# Zusatzplatine.net
KiCad netlist of a schematic drawn in EAGLE
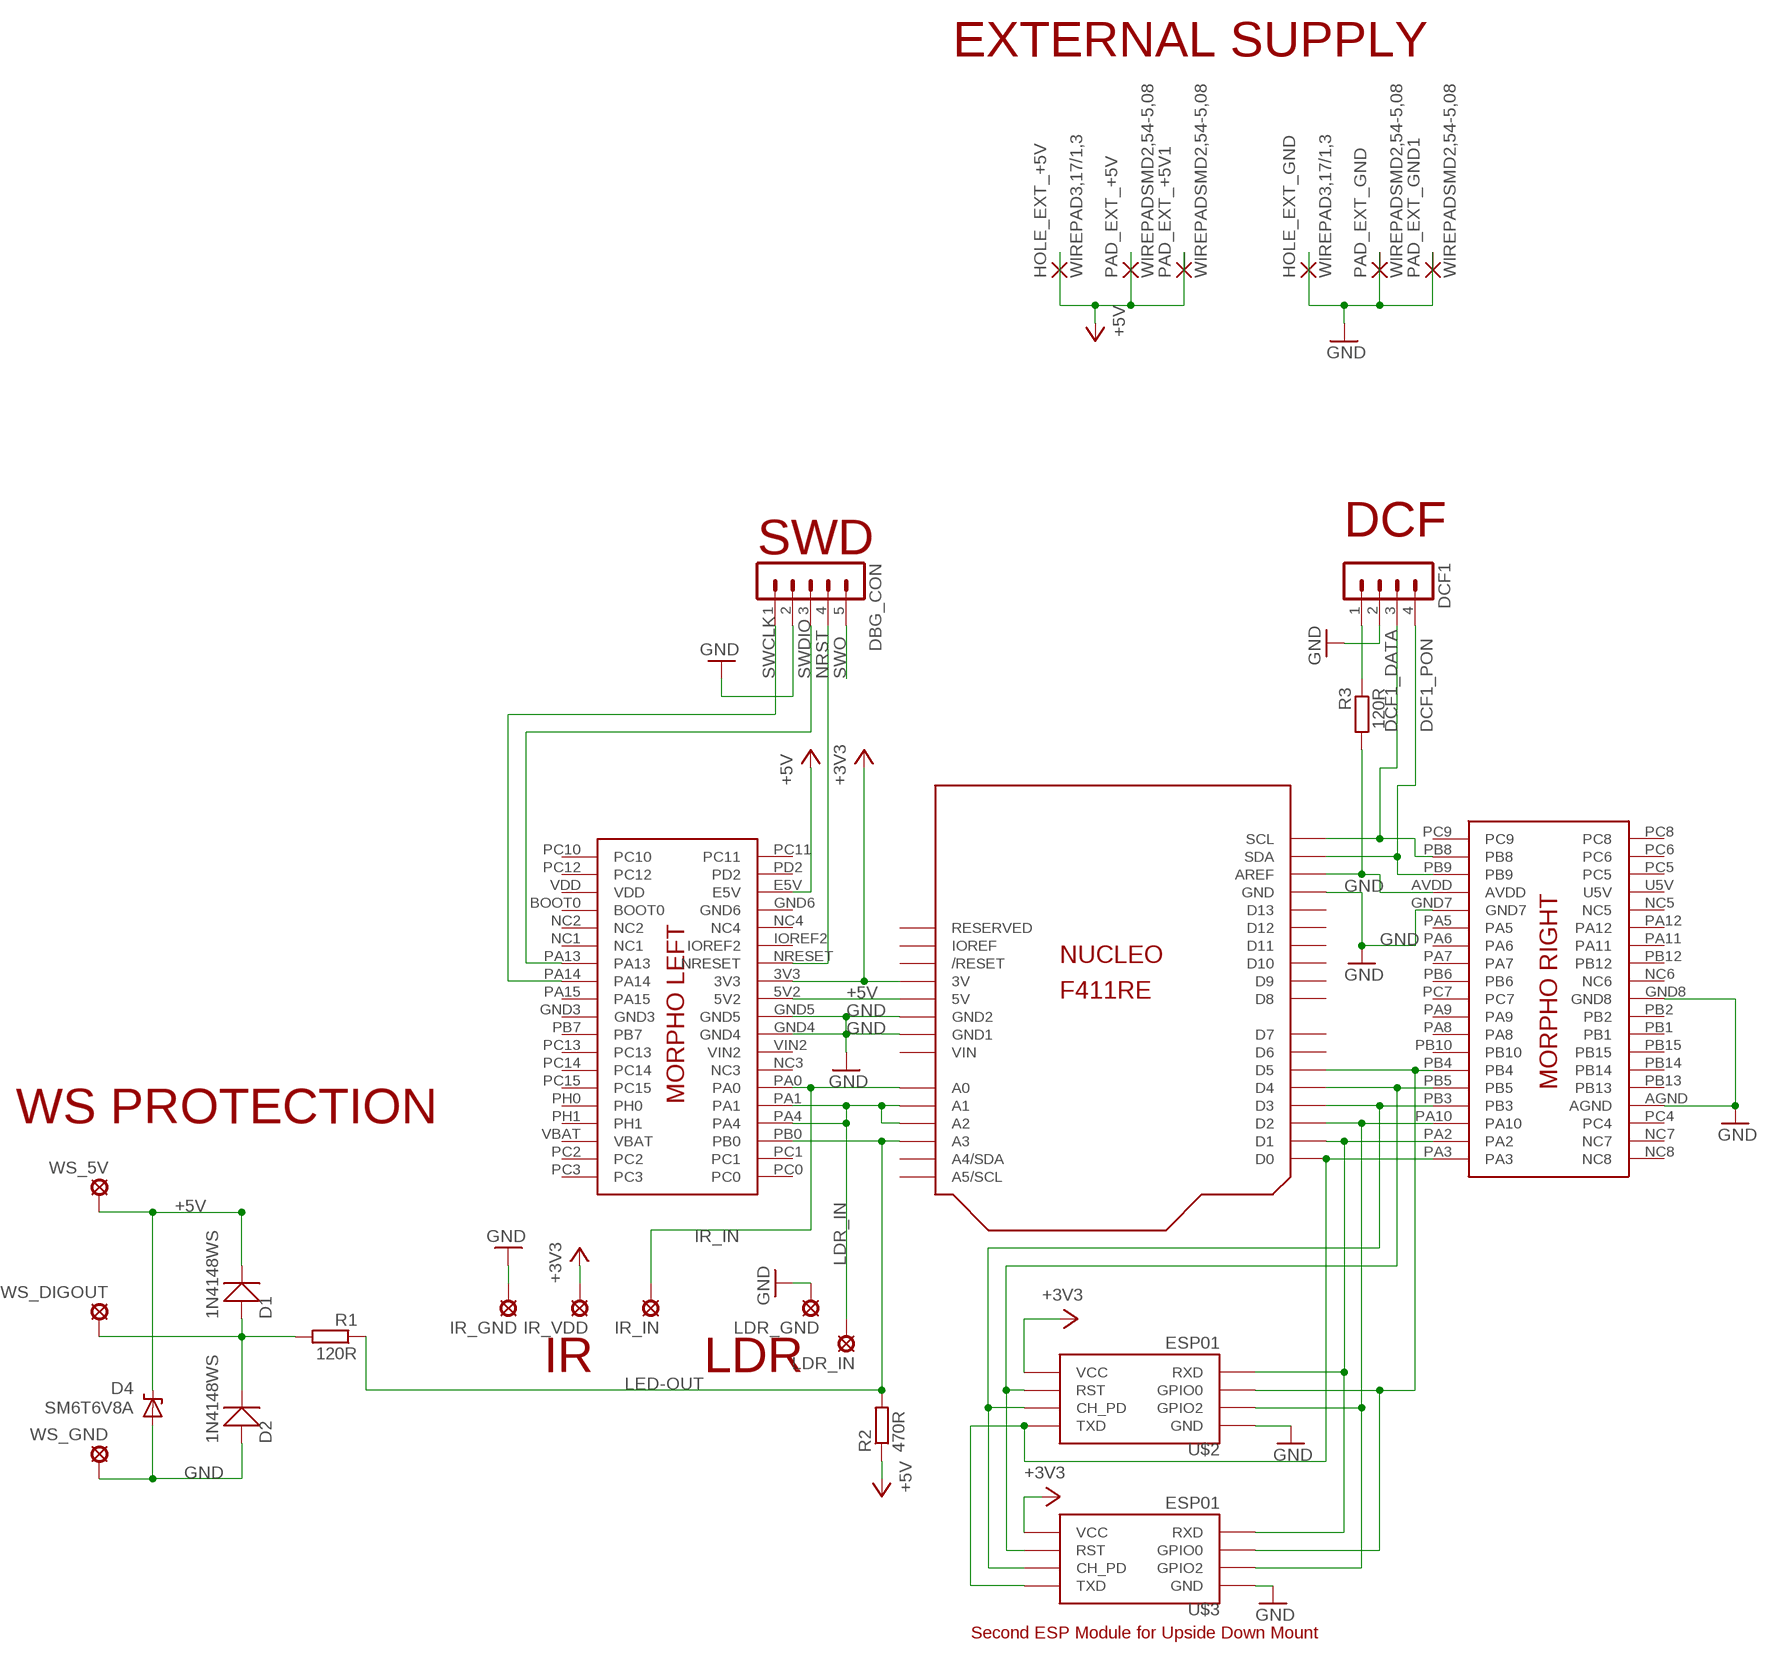
[diagram p0: schematic, sheet 1]

(export (version "E")
  (design (tool "Eeschema 10.0.6"))
  (components
    (comp (ref "D1")
      (value "1N4148WS")
      (footprint "eagle-import:SOD-323")
      (libsource (lib "eagle-import") (part "1N4148WS"))
    )
    (comp (ref "D2")
      (value "1N4148WS")
      (footprint "eagle-import:SOD-323")
      (libsource (lib "eagle-import") (part "1N4148WS"))
    )
    (comp (ref "D4")
      (value "SM6T6V8A")
      (footprint "eagle-import:SMBJ")
      (libsource (lib "eagle-import") (part "SUPPRESSOR-SMBJ"))
    )
    (comp (ref "DBG_CON")
      (value "MA05-1")
      (footprint "eagle-import:MA05-1")
      (libsource (lib "eagle-import") (part "MA05-1"))
    )
    (comp (ref "DCF1")
      (value "MA04-1")
      (footprint "eagle-import:MA04-1")
      (libsource (lib "eagle-import") (part "MA04-1"))
    )
    (comp (ref "HOLE_EXT_+5V")
      (value "WIREPAD3,17/1,3")
      (footprint "eagle-import:3,17_1,3")
      (libsource (lib "eagle-import") (part "WIREPAD3,17/1,3"))
    )
    (comp (ref "HOLE_EXT_GND")
      (value "WIREPAD3,17/1,3")
      (footprint "eagle-import:3,17_1,3")
      (libsource (lib "eagle-import") (part "WIREPAD3,17/1,3"))
    )
    (comp (ref "IR_GND")
      (value "SE14")
      (footprint "eagle-import:SE14")
      (libsource (lib "eagle-import") (part "SE14"))
    )
    (comp (ref "IR_IN")
      (value "SE14")
      (footprint "eagle-import:SE14")
      (libsource (lib "eagle-import") (part "SE14"))
    )
    (comp (ref "IR_VDD")
      (value "SE14")
      (footprint "eagle-import:SE14")
      (libsource (lib "eagle-import") (part "SE14"))
    )
    (comp (ref "LDR_GND")
      (value "SE14")
      (footprint "eagle-import:SE14")
      (libsource (lib "eagle-import") (part "SE14"))
    )
    (comp (ref "LDR_IN")
      (value "SE14")
      (footprint "eagle-import:SE14")
      (libsource (lib "eagle-import") (part "SE14"))
    )
    (comp (ref "PAD_EXT_+5V")
      (value "WIREPADSMD2,54-5,08")
      (footprint "eagle-import:SMD2,54-5,08")
      (libsource (lib "eagle-import") (part "WIREPADSMD2,54-5,08"))
    )
    (comp (ref "PAD_EXT_+5V1")
      (value "WIREPADSMD2,54-5,08")
      (footprint "eagle-import:SMD2,54-5,08")
      (libsource (lib "eagle-import") (part "WIREPADSMD2,54-5,08"))
    )
    (comp (ref "PAD_EXT_GND")
      (value "WIREPADSMD2,54-5,08")
      (footprint "eagle-import:SMD2,54-5,08")
      (libsource (lib "eagle-import") (part "WIREPADSMD2,54-5,08"))
    )
    (comp (ref "PAD_EXT_GND1")
      (value "WIREPADSMD2,54-5,08")
      (footprint "eagle-import:SMD2,54-5,08")
      (libsource (lib "eagle-import") (part "WIREPADSMD2,54-5,08"))
    )
    (comp (ref "R1")
      (value "120R")
      (footprint "eagle-import:R1206")
      (libsource (lib "eagle-import") (part "R-EU_R1206"))
    )
    (comp (ref "R2")
      (value "470R")
      (footprint "eagle-import:R1206")
      (libsource (lib "eagle-import") (part "R-EU_R1206"))
    )
    (comp (ref "R3")
      (value "120R")
      (footprint "eagle-import:R1206")
      (libsource (lib "eagle-import") (part "R-EU_R1206"))
    )
    (comp (ref "U$1")
      (value "NUCLEO_F411RE")
      (footprint "eagle-import:NUCLEO_BRD64")
      (libsource (lib "eagle-import") (part "NUCLEO_F411RE"))
    )
    (comp (ref "U$2")
      (value "ESP01")
      (footprint "eagle-import:ESP01")
      (libsource (lib "eagle-import") (part "ESP01"))
    )
    (comp (ref "U$3")
      (value "ESP01")
      (footprint "eagle-import:ESP01")
      (libsource (lib "eagle-import") (part "ESP01"))
    )
    (comp (ref "WS_5V")
      (value "SE14")
      (footprint "eagle-import:SE14")
      (libsource (lib "eagle-import") (part "SE14"))
    )
    (comp (ref "WS_DIGOUT")
      (value "SE14")
      (footprint "eagle-import:SE14")
      (libsource (lib "eagle-import") (part "SE14"))
    )
    (comp (ref "WS_GND")
      (value "SE14")
      (footprint "eagle-import:SE14")
      (libsource (lib "eagle-import") (part "SE14"))
    )
  )
  (nets
    (net (code "1") (name "+3V3") (class "Default")
      (node (ref "IR_VDD") (pin "MP") (pinfunction "MP_MP") (pintype "passive"))
      (node (ref "U$1") (pin "3V") (pinfunction "3V_3V") (pintype "power_in"))
      (node (ref "U$1") (pin "3V3") (pinfunction "3V3_3V3") (pintype "power_in"))
      (node (ref "U$2") (pin "VCC") (pinfunction "VCC_VCC") (pintype "bidirectional"))
      (node (ref "U$3") (pin "VCC") (pinfunction "VCC_VCC") (pintype "bidirectional"))
    )
    (net (code "2") (name "+5V") (class "Default")
      (node (ref "D1") (pin "1") (pinfunction "1_1") (pintype "bidirectional"))
      (node (ref "D4") (pin "C") (pinfunction "C_C") (pintype "passive"))
      (node (ref "HOLE_EXT_+5V") (pin "1") (pinfunction "P_1") (pintype "passive"))
      (node (ref "PAD_EXT_+5V") (pin "1") (pinfunction "P_1") (pintype "passive"))
      (node (ref "PAD_EXT_+5V1") (pin "1") (pinfunction "P_1") (pintype "passive"))
      (node (ref "R2") (pin "1") (pinfunction "1_1") (pintype "passive"))
      (node (ref "U$1") (pin "5V") (pinfunction "5V_5V") (pintype "power_in"))
      (node (ref "U$1") (pin "5V2") (pinfunction "5V2_5V2") (pintype "power_in"))
      (node (ref "U$1") (pin "E5V") (pinfunction "E5V_E5V") (pintype "power_in"))
      (node (ref "WS_5V") (pin "MP") (pinfunction "MP_MP") (pintype "passive"))
    )
    (net (code "3") (name "/DCF1_DATA") (class "Default")
      (node (ref "DCF1") (pin "3") (pinfunction "3_3") (pintype "passive"))
      (node (ref "U$1") (pin "PB8") (pinfunction "PB8_PB8") (pintype "bidirectional"))
      (node (ref "U$1") (pin "SCL") (pinfunction "SCL_SCL") (pintype "bidirectional"))
    )
    (net (code "4") (name "/DCF1_PON") (class "Default")
      (node (ref "DCF1") (pin "4") (pinfunction "4_4") (pintype "passive"))
      (node (ref "U$1") (pin "PB9") (pinfunction "PB9_PB9") (pintype "bidirectional"))
      (node (ref "U$1") (pin "SDA") (pinfunction "SDA_SDA") (pintype "bidirectional"))
    )
    (net (code "5") (name "/GND3") (class "Default")
      (node (ref "U$1") (pin "GND3") (pinfunction "GND3_GND3") (pintype "power_in"))
    )
    (net (code "6") (name "/GND6") (class "Default")
      (node (ref "U$1") (pin "GND6") (pinfunction "GND6_GND6") (pintype "power_in"))
    )
    (net (code "7") (name "/IR_IN") (class "Default")
      (node (ref "IR_IN") (pin "MP") (pinfunction "MP_MP") (pintype "passive"))
      (node (ref "U$1") (pin "A0") (pinfunction "A0_A0") (pintype "bidirectional"))
      (node (ref "U$1") (pin "PA0") (pinfunction "PA0_PA0") (pintype "bidirectional"))
    )
    (net (code "8") (name "/LDR_IN") (class "Default")
      (node (ref "LDR_IN") (pin "MP") (pinfunction "MP_MP") (pintype "passive"))
      (node (ref "U$1") (pin "A1") (pinfunction "A1_A1") (pintype "bidirectional"))
      (node (ref "U$1") (pin "A2") (pinfunction "A2_A2") (pintype "bidirectional"))
      (node (ref "U$1") (pin "PA1") (pinfunction "PA1_PA1") (pintype "bidirectional"))
      (node (ref "U$1") (pin "PA4") (pinfunction "PA4_PA4") (pintype "bidirectional"))
    )
    (net (code "9") (name "/LED-OUT") (class "Default")
      (node (ref "R1") (pin "1") (pinfunction "1_1") (pintype "passive"))
      (node (ref "R2") (pin "2") (pinfunction "2_2") (pintype "passive"))
      (node (ref "U$1") (pin "A3") (pinfunction "A3_A3") (pintype "bidirectional"))
      (node (ref "U$1") (pin "PB0") (pinfunction "PB0_PB0") (pintype "bidirectional"))
    )
    (net (code "10") (name "/NRST") (class "Default")
      (node (ref "DBG_CON") (pin "4") (pinfunction "4_4") (pintype "passive"))
      (node (ref "U$1") (pin "NRESET") (pinfunction "NRESET_NRESET") (pintype "input"))
    )
    (net (code "11") (name "/SWCLK") (class "Default")
      (node (ref "DBG_CON") (pin "1") (pinfunction "1_1") (pintype "passive"))
      (node (ref "U$1") (pin "PA14") (pinfunction "PA14_PA14") (pintype "bidirectional"))
    )
    (net (code "12") (name "/SWDIO") (class "Default")
      (node (ref "DBG_CON") (pin "3") (pinfunction "3_3") (pintype "passive"))
      (node (ref "U$1") (pin "PA13") (pinfunction "PA13_PA13") (pintype "bidirectional"))
    )
    (net (code "13") (name "/SWO") (class "Default")
      (node (ref "DBG_CON") (pin "5") (pinfunction "5_5") (pintype "passive"))
    )
    (net (code "14") (name "/U5V") (class "Default")
      (node (ref "U$1") (pin "U5V") (pinfunction "U5V_U5V") (pintype "power_in"))
    )
    (net (code "15") (name "/VBAT") (class "Default")
      (node (ref "U$1") (pin "VBAT") (pinfunction "VBAT_VBAT") (pintype "power_in"))
    )
    (net (code "16") (name "/VDD") (class "Default")
      (node (ref "U$1") (pin "VDD") (pinfunction "VDD_VDD") (pintype "power_in"))
    )
    (net (code "17") (name "/VIN") (class "Default")
      (node (ref "U$1") (pin "VIN") (pinfunction "VIN_VIN") (pintype "power_in"))
    )
    (net (code "18") (name "/VIN2") (class "Default")
      (node (ref "U$1") (pin "VIN2") (pinfunction "VIN2_VIN2") (pintype "power_in"))
    )
    (net (code "19") (name "GND") (class "Default")
      (node (ref "D2") (pin "0") (pinfunction "0_0") (pintype "bidirectional"))
      (node (ref "D4") (pin "A") (pinfunction "A_A") (pintype "passive"))
      (node (ref "DBG_CON") (pin "2") (pinfunction "2_2") (pintype "passive"))
      (node (ref "DCF1") (pin "2") (pinfunction "2_2") (pintype "passive"))
      (node (ref "HOLE_EXT_GND") (pin "1") (pinfunction "P_1") (pintype "passive"))
      (node (ref "IR_GND") (pin "MP") (pinfunction "MP_MP") (pintype "passive"))
      (node (ref "LDR_GND") (pin "MP") (pinfunction "MP_MP") (pintype "passive"))
      (node (ref "PAD_EXT_GND") (pin "1") (pinfunction "P_1") (pintype "passive"))
      (node (ref "PAD_EXT_GND1") (pin "1") (pinfunction "P_1") (pintype "passive"))
      (node (ref "U$1") (pin "AGND") (pinfunction "AGND_AGND") (pintype "power_in"))
      (node (ref "U$1") (pin "GND") (pinfunction "GND_GND") (pintype "power_in"))
      (node (ref "U$1") (pin "GND1") (pinfunction "GND1_GND1") (pintype "power_in"))
      (node (ref "U$1") (pin "GND2") (pinfunction "GND2_GND2") (pintype "power_in"))
      (node (ref "U$1") (pin "GND4") (pinfunction "GND4_GND4") (pintype "power_in"))
      (node (ref "U$1") (pin "GND5") (pinfunction "GND5_GND5") (pintype "power_in"))
      (node (ref "U$1") (pin "GND7") (pinfunction "GND7_GND7") (pintype "power_in"))
      (node (ref "U$1") (pin "GND8") (pinfunction "GND8_GND8") (pintype "power_in"))
      (node (ref "U$2") (pin "GND") (pinfunction "GND_GND") (pintype "bidirectional"))
      (node (ref "U$3") (pin "GND") (pinfunction "GND_GND") (pintype "bidirectional"))
      (node (ref "WS_GND") (pin "MP") (pinfunction "MP_MP") (pintype "passive"))
    )
    (net (code "20") (name "Net-(D1-Pad0)") (class "Default")
      (node (ref "D1") (pin "0") (pinfunction "0_0") (pintype "bidirectional"))
      (node (ref "D2") (pin "1") (pinfunction "1_1") (pintype "bidirectional"))
      (node (ref "R1") (pin "2") (pinfunction "2_2") (pintype "passive"))
      (node (ref "WS_DIGOUT") (pin "MP") (pinfunction "MP_MP") (pintype "passive"))
    )
    (net (code "21") (name "Net-(DCF1-Pad1)") (class "Default")
      (node (ref "DCF1") (pin "1") (pinfunction "1_1") (pintype "passive"))
      (node (ref "R3") (pin "1") (pinfunction "1_1") (pintype "passive"))
    )
    (net (code "22") (name "Net-(R3-Pad2)") (class "Default")
      (node (ref "R3") (pin "2") (pinfunction "2_2") (pintype "passive"))
      (node (ref "U$1") (pin "AREF") (pinfunction "AREF_AREF") (pintype "bidirectional"))
      (node (ref "U$1") (pin "AVDD") (pinfunction "AVDD_AVDD") (pintype "power_in"))
    )
    (net (code "23") (name "Net-(U$1-PadD2)") (class "Default")
      (node (ref "U$1") (pin "D2") (pinfunction "D2_D2") (pintype "bidirectional"))
      (node (ref "U$1") (pin "PA10") (pinfunction "PA10_PA10") (pintype "bidirectional"))
      (node (ref "U$2") (pin "GPIO2") (pinfunction "GPIO2_GPIO2") (pintype "bidirectional"))
      (node (ref "U$3") (pin "GPIO2") (pinfunction "GPIO2_GPIO2") (pintype "bidirectional"))
    )
    (net (code "24") (name "Net-(U$1-PadD3)") (class "Default")
      (node (ref "U$1") (pin "D3") (pinfunction "D3_D3") (pintype "bidirectional"))
      (node (ref "U$1") (pin "PB3") (pinfunction "PB3_PB3") (pintype "bidirectional"))
      (node (ref "U$2") (pin "CH_PD") (pinfunction "CH_PD_CH_PD") (pintype "bidirectional"))
      (node (ref "U$3") (pin "CH_PD") (pinfunction "CH_PD_CH_PD") (pintype "bidirectional"))
    )
    (net (code "25") (name "Net-(U$1-PadD4)") (class "Default")
      (node (ref "U$1") (pin "D4") (pinfunction "D4_D4") (pintype "bidirectional"))
      (node (ref "U$1") (pin "PB5") (pinfunction "PB5_PB5") (pintype "bidirectional"))
      (node (ref "U$2") (pin "RST") (pinfunction "RST_RST") (pintype "bidirectional"))
      (node (ref "U$3") (pin "RST") (pinfunction "RST_RST") (pintype "bidirectional"))
    )
    (net (code "26") (name "Net-(U$1-PadD5)") (class "Default")
      (node (ref "U$1") (pin "D5") (pinfunction "D5_D5") (pintype "bidirectional"))
      (node (ref "U$1") (pin "PB4") (pinfunction "PB4_PB4") (pintype "bidirectional"))
      (node (ref "U$2") (pin "GPIO0") (pinfunction "GPIO0_GPIO0") (pintype "bidirectional"))
      (node (ref "U$3") (pin "GPIO0") (pinfunction "GPIO0_GPIO0") (pintype "bidirectional"))
    )
    (net (code "27") (name "Net-(U$2-RXD)") (class "Default")
      (node (ref "U$1") (pin "D1") (pinfunction "D1_D1") (pintype "bidirectional"))
      (node (ref "U$1") (pin "PA2") (pinfunction "PA2_PA2") (pintype "bidirectional"))
      (node (ref "U$2") (pin "RX") (pinfunction "RXD_RX") (pintype "bidirectional"))
      (node (ref "U$3") (pin "RX") (pinfunction "RXD_RX") (pintype "bidirectional"))
    )
    (net (code "28") (name "Net-(U$2-TXD)") (class "Default")
      (node (ref "U$1") (pin "D0") (pinfunction "D0_D0") (pintype "bidirectional"))
      (node (ref "U$1") (pin "PA3") (pinfunction "PA3_PA3") (pintype "bidirectional"))
      (node (ref "U$2") (pin "TX") (pinfunction "TXD_TX") (pintype "bidirectional"))
      (node (ref "U$3") (pin "TX") (pinfunction "TXD_TX") (pintype "bidirectional"))
    )
    (net (code "29") (name "unconnected-(U$1-A4{slash}SDA-PadA4)") (class "Default")
      (node (ref "U$1") (pin "A4") (pinfunction "A4/SDA_A4") (pintype "bidirectional"))
    )
    (net (code "30") (name "unconnected-(U$1-A5{slash}SCL-PadA5)") (class "Default")
      (node (ref "U$1") (pin "A5") (pinfunction "A5/SCL_A5") (pintype "bidirectional"))
    )
    (net (code "31") (name "unconnected-(U$1-PadBOOT0)") (class "Default")
      (node (ref "U$1") (pin "BOOT0") (pinfunction "BOOT0_BOOT0") (pintype "bidirectional"))
    )
    (net (code "32") (name "unconnected-(U$1-PadD6)") (class "Default")
      (node (ref "U$1") (pin "D6") (pinfunction "D6_D6") (pintype "bidirectional"))
    )
    (net (code "33") (name "unconnected-(U$1-PadD7)") (class "Default")
      (node (ref "U$1") (pin "D7") (pinfunction "D7_D7") (pintype "bidirectional"))
    )
    (net (code "34") (name "unconnected-(U$1-PadD8)") (class "Default")
      (node (ref "U$1") (pin "D8") (pinfunction "D8_D8") (pintype "bidirectional"))
    )
    (net (code "35") (name "unconnected-(U$1-PadD9)") (class "Default")
      (node (ref "U$1") (pin "D9") (pinfunction "D9_D9") (pintype "bidirectional"))
    )
    (net (code "36") (name "unconnected-(U$1-PadD10)") (class "Default")
      (node (ref "U$1") (pin "D10") (pinfunction "D10_D10") (pintype "bidirectional"))
    )
    (net (code "37") (name "unconnected-(U$1-PadD11)") (class "Default")
      (node (ref "U$1") (pin "D11") (pinfunction "D11_D11") (pintype "bidirectional"))
    )
    (net (code "38") (name "unconnected-(U$1-PadD12)") (class "Default")
      (node (ref "U$1") (pin "D12") (pinfunction "D12_D12") (pintype "bidirectional"))
    )
    (net (code "39") (name "unconnected-(U$1-PadD13)") (class "Default")
      (node (ref "U$1") (pin "D13") (pinfunction "D13_D13") (pintype "bidirectional"))
    )
    (net (code "40") (name "unconnected-(U$1-PadIOREF)") (class "Default")
      (node (ref "U$1") (pin "IOREF") (pinfunction "IOREF_IOREF") (pintype "output"))
    )
    (net (code "41") (name "unconnected-(U$1-PadIOREF2)") (class "Default")
      (node (ref "U$1") (pin "IOREF2") (pinfunction "IOREF2_IOREF2") (pintype "input"))
    )
    (net (code "42") (name "unconnected-(U$1-PadNC1)") (class "Default")
      (node (ref "U$1") (pin "NC1") (pinfunction "NC1_NC1") (pintype "no_connect"))
    )
    (net (code "43") (name "unconnected-(U$1-PadNC2)") (class "Default")
      (node (ref "U$1") (pin "NC2") (pinfunction "NC2_NC2") (pintype "no_connect"))
    )
    (net (code "44") (name "unconnected-(U$1-PadNC3)") (class "Default")
      (node (ref "U$1") (pin "NC3") (pinfunction "NC3_NC3") (pintype "no_connect"))
    )
    (net (code "45") (name "unconnected-(U$1-PadNC4)") (class "Default")
      (node (ref "U$1") (pin "NC4") (pinfunction "NC4_NC4") (pintype "no_connect"))
    )
    (net (code "46") (name "unconnected-(U$1-PadNC5)") (class "Default")
      (node (ref "U$1") (pin "NC5") (pinfunction "NC5_NC5") (pintype "no_connect"))
    )
    (net (code "47") (name "unconnected-(U$1-PadNC6)") (class "Default")
      (node (ref "U$1") (pin "NC6") (pinfunction "NC6_NC6") (pintype "no_connect"))
    )
    (net (code "48") (name "unconnected-(U$1-PadNC7)") (class "Default")
      (node (ref "U$1") (pin "NC7") (pinfunction "NC7_NC7") (pintype "no_connect"))
    )
    (net (code "49") (name "unconnected-(U$1-PadNC8)") (class "Default")
      (node (ref "U$1") (pin "NC8") (pinfunction "NC8_NC8") (pintype "no_connect"))
    )
    (net (code "50") (name "unconnected-(U$1-PadPA5)") (class "Default")
      (node (ref "U$1") (pin "PA5") (pinfunction "PA5_PA5") (pintype "bidirectional"))
    )
    (net (code "51") (name "unconnected-(U$1-PadPA6)") (class "Default")
      (node (ref "U$1") (pin "PA6") (pinfunction "PA6_PA6") (pintype "bidirectional"))
    )
    (net (code "52") (name "unconnected-(U$1-PadPA7)") (class "Default")
      (node (ref "U$1") (pin "PA7") (pinfunction "PA7_PA7") (pintype "bidirectional"))
    )
    (net (code "53") (name "unconnected-(U$1-PadPA8)") (class "Default")
      (node (ref "U$1") (pin "PA8") (pinfunction "PA8_PA8") (pintype "bidirectional"))
    )
    (net (code "54") (name "unconnected-(U$1-PadPA9)") (class "Default")
      (node (ref "U$1") (pin "PA9") (pinfunction "PA9_PA9") (pintype "bidirectional"))
    )
    (net (code "55") (name "unconnected-(U$1-PadPA11)") (class "Default")
      (node (ref "U$1") (pin "PA11") (pinfunction "PA11_PA11") (pintype "bidirectional"))
    )
    (net (code "56") (name "unconnected-(U$1-PadPA12)") (class "Default")
      (node (ref "U$1") (pin "PA12") (pinfunction "PA12_PA12") (pintype "bidirectional"))
    )
    (net (code "57") (name "unconnected-(U$1-PadPA15)") (class "Default")
      (node (ref "U$1") (pin "PA15") (pinfunction "PA15_PA15") (pintype "bidirectional"))
    )
    (net (code "58") (name "unconnected-(U$1-PadPB1)") (class "Default")
      (node (ref "U$1") (pin "PB1") (pinfunction "PB1_PB1") (pintype "bidirectional"))
    )
    (net (code "59") (name "unconnected-(U$1-PadPB2)") (class "Default")
      (node (ref "U$1") (pin "PB2") (pinfunction "PB2_PB2") (pintype "bidirectional"))
    )
    (net (code "60") (name "unconnected-(U$1-PadPB6)") (class "Default")
      (node (ref "U$1") (pin "PB6") (pinfunction "PB6_PB6") (pintype "bidirectional"))
    )
    (net (code "61") (name "unconnected-(U$1-PadPB7)") (class "Default")
      (node (ref "U$1") (pin "PB7") (pinfunction "PB7_PB7") (pintype "bidirectional"))
    )
    (net (code "62") (name "unconnected-(U$1-PadPB10)") (class "Default")
      (node (ref "U$1") (pin "PB10") (pinfunction "PB10_PB10") (pintype "bidirectional"))
    )
    (net (code "63") (name "unconnected-(U$1-PadPB12)") (class "Default")
      (node (ref "U$1") (pin "PB12") (pinfunction "PB12_PB12") (pintype "bidirectional"))
    )
    (net (code "64") (name "unconnected-(U$1-PadPB13)") (class "Default")
      (node (ref "U$1") (pin "PB13") (pinfunction "PB13_PB13") (pintype "bidirectional"))
    )
    (net (code "65") (name "unconnected-(U$1-PadPB14)") (class "Default")
      (node (ref "U$1") (pin "PB14") (pinfunction "PB14_PB14") (pintype "bidirectional"))
    )
    (net (code "66") (name "unconnected-(U$1-PadPB15)") (class "Default")
      (node (ref "U$1") (pin "PB15") (pinfunction "PB15_PB15") (pintype "bidirectional"))
    )
    (net (code "67") (name "unconnected-(U$1-PadPC0)") (class "Default")
      (node (ref "U$1") (pin "PC0") (pinfunction "PC0_PC0") (pintype "bidirectional"))
    )
    (net (code "68") (name "unconnected-(U$1-PadPC1)") (class "Default")
      (node (ref "U$1") (pin "PC1") (pinfunction "PC1_PC1") (pintype "bidirectional"))
    )
    (net (code "69") (name "unconnected-(U$1-PadPC2)") (class "Default")
      (node (ref "U$1") (pin "PC2") (pinfunction "PC2_PC2") (pintype "bidirectional"))
    )
    (net (code "70") (name "unconnected-(U$1-PadPC3)") (class "Default")
      (node (ref "U$1") (pin "PC3") (pinfunction "PC3_PC3") (pintype "bidirectional"))
    )
    (net (code "71") (name "unconnected-(U$1-PadPC4)") (class "Default")
      (node (ref "U$1") (pin "PC4") (pinfunction "PC4_PC4") (pintype "bidirectional"))
    )
    (net (code "72") (name "unconnected-(U$1-PadPC5)") (class "Default")
      (node (ref "U$1") (pin "PC5") (pinfunction "PC5_PC5") (pintype "bidirectional"))
    )
    (net (code "73") (name "unconnected-(U$1-PadPC6)") (class "Default")
      (node (ref "U$1") (pin "PC6") (pinfunction "PC6_PC6") (pintype "bidirectional"))
    )
    (net (code "74") (name "unconnected-(U$1-PadPC7)") (class "Default")
      (node (ref "U$1") (pin "PC7") (pinfunction "PC7_PC7") (pintype "bidirectional"))
    )
    (net (code "75") (name "unconnected-(U$1-PadPC8)") (class "Default")
      (node (ref "U$1") (pin "PC8") (pinfunction "PC8_PC8") (pintype "bidirectional"))
    )
    (net (code "76") (name "unconnected-(U$1-PadPC9)") (class "Default")
      (node (ref "U$1") (pin "PC9") (pinfunction "PC9_PC9") (pintype "bidirectional"))
    )
    (net (code "77") (name "unconnected-(U$1-PadPC10)") (class "Default")
      (node (ref "U$1") (pin "PC10") (pinfunction "PC10_PC10") (pintype "bidirectional"))
    )
    (net (code "78") (name "unconnected-(U$1-PadPC11)") (class "Default")
      (node (ref "U$1") (pin "PC11") (pinfunction "PC11_PC11") (pintype "bidirectional"))
    )
    (net (code "79") (name "unconnected-(U$1-PadPC12)") (class "Default")
      (node (ref "U$1") (pin "PC12") (pinfunction "PC12_PC12") (pintype "bidirectional"))
    )
    (net (code "80") (name "unconnected-(U$1-PadPC13)") (class "Default")
      (node (ref "U$1") (pin "PC13") (pinfunction "PC13_PC13") (pintype "bidirectional"))
    )
    (net (code "81") (name "unconnected-(U$1-PadPC14)") (class "Default")
      (node (ref "U$1") (pin "PC14") (pinfunction "PC14_PC14") (pintype "bidirectional"))
    )
    (net (code "82") (name "unconnected-(U$1-PadPC15)") (class "Default")
      (node (ref "U$1") (pin "PC15") (pinfunction "PC15_PC15") (pintype "bidirectional"))
    )
    (net (code "83") (name "unconnected-(U$1-PadPD2)") (class "Default")
      (node (ref "U$1") (pin "PD2") (pinfunction "PD2_PD2") (pintype "bidirectional"))
    )
    (net (code "84") (name "unconnected-(U$1-PadPH0)") (class "Default")
      (node (ref "U$1") (pin "PH0") (pinfunction "PH0_PH0") (pintype "bidirectional"))
    )
    (net (code "85") (name "unconnected-(U$1-PadPH1)") (class "Default")
      (node (ref "U$1") (pin "PH1") (pinfunction "PH1_PH1") (pintype "bidirectional"))
    )
    (net (code "86") (name "unconnected-(U$1-PadRESERVED)") (class "Default")
      (node (ref "U$1") (pin "RESERVED") (pinfunction "RESERVED_RESERVED") (pintype "no_connect"))
    )
    (net (code "87") (name "unconnected-(U$1-{slash}RESET-PadRESET)") (class "Default")
      (node (ref "U$1") (pin "RESET") (pinfunction "/RESET_RESET") (pintype "bidirectional"))
    )
  )
)
